# Analog_Front_End.net
KiCad netlist of a schematic drawn in Altium Designer
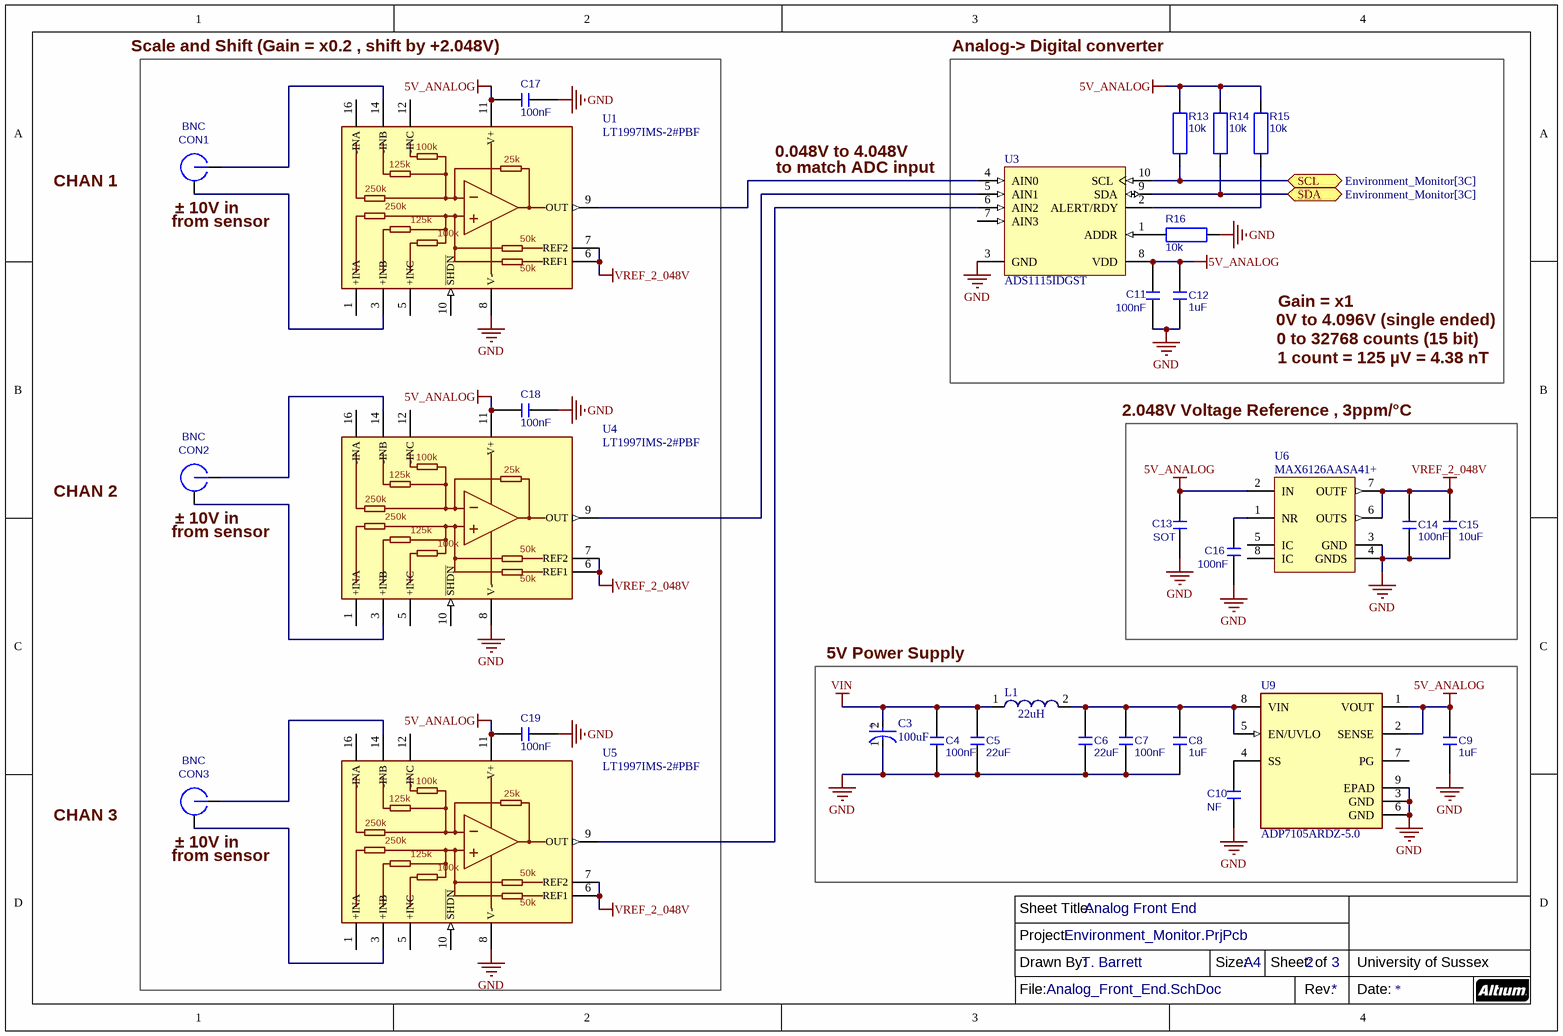
[diagram p0: Analog_Front_End.SchDoc]

(export (version "E")
  (design (tool "Eeschema 10.0.6"))
  (components
    (comp (ref "C3")
      (value "100uF")
      (footprint "FP-865080657017-MFG")
      (description "CAP ALUM 150UF 20% 50V SMD")
      (fields (field (name "TOLERANCE") "20%"))
      (libsource (lib "Altium Content Vault") (part "cf48714ba7e38822c1575c7ec0b6d1f"))
    )
    (comp (ref "C4")
      (value "100nF")
      (footprint "CAPACITOR SMD 1206")
      (description "Ceramic chip capacitor 1206")
      (fields (field (name "Comment") "Capacitor SMD 1206"))
      (libsource (lib "TB_Capacitors") (part "Capacitor SMD 1206"))
    )
    (comp (ref "C5")
      (value "22uF")
      (footprint "CAPACITOR SMD 1206")
      (description "Ceramic chip capacitor 1206")
      (fields (field (name "Comment") "Capacitor SMD 1206"))
      (libsource (lib "TB_Capacitors") (part "Capacitor SMD 1206"))
    )
    (comp (ref "C6")
      (value "22uF")
      (footprint "CAPACITOR SMD 1206")
      (description "Ceramic chip capacitor 1206")
      (fields (field (name "Comment") "Capacitor SMD 1206"))
      (libsource (lib "TB_Capacitors") (part "Capacitor SMD 1206"))
    )
    (comp (ref "C7")
      (value "100nF")
      (footprint "CAPACITOR SMD 1206")
      (description "Ceramic chip capacitor 1206")
      (fields (field (name "Comment") "Capacitor SMD 1206"))
      (libsource (lib "TB_Capacitors") (part "Capacitor SMD 1206"))
    )
    (comp (ref "C8")
      (value "1uF")
      (footprint "CAPACITOR SMD 1206")
      (description "Ceramic chip capacitor 1206")
      (fields (field (name "Comment") "Capacitor SMD 1206"))
      (libsource (lib "TB_Capacitors") (part "Capacitor SMD 1206"))
    )
    (comp (ref "C9")
      (value "1uF")
      (footprint "CAPACITOR SMD 1206")
      (description "Ceramic chip capacitor 1206")
      (fields (field (name "Comment") "Capacitor SMD 1206"))
      (libsource (lib "TB_Capacitors") (part "Capacitor SMD 1206"))
    )
    (comp (ref "C10")
      (value "NF")
      (footprint "CAPACITOR SMD 0805")
      (description "Ceramic chip capacitor 0805")
      (fields (field (name "Comment") "Capacitor SMD 0805"))
      (libsource (lib "TB_Capacitors") (part "Capacitor SMD 0805"))
    )
    (comp (ref "C11")
      (value "100nF")
      (footprint "CAPACITOR SMD 0805")
      (description "Ceramic chip capacitor 0805")
      (fields (field (name "Comment") "Capacitor SMD 0805"))
      (libsource (lib "TB_Capacitors") (part "Capacitor SMD 0805"))
    )
    (comp (ref "C12")
      (value "1uF")
      (footprint "CAPACITOR SMD 1206")
      (description "Ceramic chip capacitor 1206")
      (fields (field (name "Comment") "Capacitor SMD 1206"))
      (libsource (lib "TB_Capacitors") (part "Capacitor SMD 1206"))
    )
    (comp (ref "C13")
      (value "SOT")
      (footprint "CAPACITOR SMD 1206")
      (description "Ceramic chip capacitor 1206")
      (fields (field (name "Comment") "Capacitor SMD 1206"))
      (libsource (lib "TB_Capacitors") (part "Capacitor SMD 1206"))
    )
    (comp (ref "C14")
      (value "100nF")
      (footprint "CAPACITOR SMD 0805")
      (description "Ceramic chip capacitor 0805")
      (fields (field (name "Comment") "Capacitor SMD 0805"))
      (libsource (lib "TB_Capacitors") (part "Capacitor SMD 0805"))
    )
    (comp (ref "C15")
      (value "10uF")
      (footprint "CAPACITOR SMD 1206")
      (description "Ceramic chip capacitor 1206")
      (fields (field (name "Comment") "Capacitor SMD 1206"))
      (libsource (lib "TB_Capacitors") (part "Capacitor SMD 1206"))
    )
    (comp (ref "C16")
      (value "100nF")
      (footprint "CAPACITOR SMD 0805")
      (description "Ceramic chip capacitor 0805")
      (fields (field (name "Comment") "Capacitor SMD 0805"))
      (libsource (lib "TB_Capacitors") (part "Capacitor SMD 0805"))
    )
    (comp (ref "C17")
      (value "100nF")
      (footprint "CAPACITOR SMD 0805")
      (description "Ceramic chip capacitor 0805")
      (fields (field (name "Comment") "Capacitor SMD 0805"))
      (libsource (lib "TB_Capacitors") (part "Capacitor SMD 0805"))
    )
    (comp (ref "C18")
      (value "100nF")
      (footprint "CAPACITOR SMD 0805")
      (description "Ceramic chip capacitor 0805")
      (fields (field (name "Comment") "Capacitor SMD 0805"))
      (libsource (lib "TB_Capacitors") (part "Capacitor SMD 0805"))
    )
    (comp (ref "C19")
      (value "100nF")
      (footprint "CAPACITOR SMD 0805")
      (description "Ceramic chip capacitor 0805")
      (fields (field (name "Comment") "Capacitor SMD 0805"))
      (libsource (lib "TB_Capacitors") (part "Capacitor SMD 0805"))
    )
    (comp (ref "CON1")
      (value "BNC")
      (footprint "BNC B6252H5-NPP3G-50")
      (libsource (lib "TB_Connectors") (part "BNC B6252H5-NPP3G-50"))
    )
    (comp (ref "CON2")
      (value "BNC")
      (footprint "BNC B6252H5-NPP3G-50")
      (libsource (lib "TB_Connectors") (part "BNC B6252H5-NPP3G-50"))
    )
    (comp (ref "CON3")
      (value "BNC")
      (footprint "BNC B6252H5-NPP3G-50")
      (libsource (lib "TB_Connectors") (part "BNC B6252H5-NPP3G-50"))
    )
    (comp (ref "L1")
      (value "22uH")
      (footprint "WE-LQS 4018")
      (description "WE-LQS SMD Power Inductor, L=33 µH")
      (fields (field (name "MANUFACTURER") "Wuerth Elektronik") (field (name "PARTNUMBER") "74404042330"))
      (libsource (lib "Altium Content Vault") (part "WE-IND-INDUCTOR-2"))
    )
    (comp (ref "R13")
      (value "10k")
      (footprint "RESISTOR SMD 0805")
      (description "Resistor, SMD, 0805")
      (fields (field (name "Comment") "Resistor SMD 0805"))
      (libsource (lib "TB_Resistors") (part "Resistor SMD 0805"))
    )
    (comp (ref "R14")
      (value "10k")
      (footprint "RESISTOR SMD 0805")
      (description "Resistor, SMD, 0805")
      (fields (field (name "Comment") "Resistor SMD 0805"))
      (libsource (lib "TB_Resistors") (part "Resistor SMD 0805"))
    )
    (comp (ref "R15")
      (value "10k")
      (footprint "RESISTOR SMD 0805")
      (description "Resistor, SMD, 0805")
      (fields (field (name "Comment") "Resistor SMD 0805"))
      (libsource (lib "TB_Resistors") (part "Resistor SMD 0805"))
    )
    (comp (ref "R16")
      (value "10k")
      (footprint "RESISTOR SMD 0805")
      (description "Resistor, SMD, 0805")
      (fields (field (name "Comment") "Resistor SMD 0805"))
      (libsource (lib "TB_Resistors") (part "Resistor SMD 0805"))
    )
    (comp (ref "U1")
      (value "LT1997IMS-2#PBF")
      (footprint "MSOP-16 (12 pin variation)")
      (description "IC OPAMP GP 1 CIRCUIT 16MSOP")
      (libsource (lib "TB_ICs") (part "LT1997-2"))
    )
    (comp (ref "U3")
      (value "ADS1115IDGST")
      (footprint "VSSOP 10PIN")
      (fields (field (name "MANUFACTURER") "Texas Instruments"))
      (libsource (lib "TB_ICs") (part "ADS1115"))
    )
    (comp (ref "U4")
      (value "LT1997IMS-2#PBF")
      (footprint "MSOP-16 (12 pin variation)")
      (description "IC OPAMP GP 1 CIRCUIT 16MSOP")
      (libsource (lib "TB_ICs") (part "LT1997-2"))
    )
    (comp (ref "U5")
      (value "LT1997IMS-2#PBF")
      (footprint "MSOP-16 (12 pin variation)")
      (description "IC OPAMP GP 1 CIRCUIT 16MSOP")
      (libsource (lib "TB_ICs") (part "LT1997-2"))
    )
    (comp (ref "U6")
      (value "MAX6126AASA41+")
      (footprint "SOIC_N 8-pin")
      (description "Ultra-High-Precision, Ultra-Low-Noise, Series Voltage Reference, 8-Pin SOIC")
      (fields (field (name "MANUFACTURER") "Maxim"))
      (libsource (lib "TB_ICs") (part "MAX6126"))
    )
    (comp (ref "U9")
      (value "ADP7105ARDZ-5.0")
      (footprint "NSOIC-EP-8")
      (description "ANALOG DEVICES 20 V, 500 mA, Low Noise LDO Regulator")
      (libsource (lib "TB_ICs") (part "ADP7105"))
    )
  )
  (nets
    (net (code "1") (name "/SCL") (class "Default")
      (node (ref "R13") (pin "1") (pinfunction "1_1") (pintype "passive"))
      (node (ref "U3") (pin "10") (pinfunction "SCL_10") (pintype "input"))
    )
    (net (code "2") (name "/SDA") (class "Default")
      (node (ref "R14") (pin "1") (pinfunction "1_1") (pintype "passive"))
      (node (ref "U3") (pin "9") (pinfunction "SDA_9") (pintype "bidirectional"))
    )
    (net (code "3") (name "5V_ANALOG") (class "Default")
      (node (ref "C11") (pin "2") (pinfunction "2_2") (pintype "passive"))
      (node (ref "C12") (pin "2") (pinfunction "2_2") (pintype "passive"))
      (node (ref "C13") (pin "2") (pinfunction "2_2") (pintype "passive"))
      (node (ref "C17") (pin "2") (pinfunction "2_2") (pintype "passive"))
      (node (ref "C18") (pin "2") (pinfunction "2_2") (pintype "passive"))
      (node (ref "C19") (pin "2") (pinfunction "2_2") (pintype "passive"))
      (node (ref "C9") (pin "2") (pinfunction "2_2") (pintype "passive"))
      (node (ref "R13") (pin "2") (pinfunction "2_2") (pintype "passive"))
      (node (ref "R14") (pin "2") (pinfunction "2_2") (pintype "passive"))
      (node (ref "R15") (pin "2") (pinfunction "2_2") (pintype "passive"))
      (node (ref "U1") (pin "11") (pinfunction "V+_11") (pintype "power_in"))
      (node (ref "U3") (pin "8") (pinfunction "VDD_8") (pintype "power_in"))
      (node (ref "U4") (pin "11") (pinfunction "V+_11") (pintype "power_in"))
      (node (ref "U5") (pin "11") (pinfunction "V+_11") (pintype "power_in"))
      (node (ref "U6") (pin "2") (pinfunction "IN_2") (pintype "power_in"))
      (node (ref "U9") (pin "1") (pinfunction "VOUT_1") (pintype "passive"))
      (node (ref "U9") (pin "2") (pinfunction "SENSE_2") (pintype "passive"))
    )
    (net (code "4") (name "GND") (class "Default")
      (node (ref "C10") (pin "1") (pinfunction "1_1") (pintype "passive"))
      (node (ref "C11") (pin "1") (pinfunction "1_1") (pintype "passive"))
      (node (ref "C12") (pin "1") (pinfunction "1_1") (pintype "passive"))
      (node (ref "C13") (pin "1") (pinfunction "1_1") (pintype "passive"))
      (node (ref "C14") (pin "1") (pinfunction "1_1") (pintype "passive"))
      (node (ref "C15") (pin "1") (pinfunction "1_1") (pintype "passive"))
      (node (ref "C16") (pin "1") (pinfunction "1_1") (pintype "passive"))
      (node (ref "C17") (pin "1") (pinfunction "1_1") (pintype "passive"))
      (node (ref "C18") (pin "1") (pinfunction "1_1") (pintype "passive"))
      (node (ref "C19") (pin "1") (pinfunction "1_1") (pintype "passive"))
      (node (ref "C3") (pin "1") (pinfunction "C_1") (pintype "passive"))
      (node (ref "C4") (pin "1") (pinfunction "1_1") (pintype "passive"))
      (node (ref "C5") (pin "1") (pinfunction "1_1") (pintype "passive"))
      (node (ref "C6") (pin "1") (pinfunction "1_1") (pintype "passive"))
      (node (ref "C7") (pin "1") (pinfunction "1_1") (pintype "passive"))
      (node (ref "C8") (pin "1") (pinfunction "1_1") (pintype "passive"))
      (node (ref "C9") (pin "1") (pinfunction "1_1") (pintype "passive"))
      (node (ref "R16") (pin "1") (pinfunction "1_1") (pintype "passive"))
      (node (ref "U1") (pin "8") (pinfunction "V-_8") (pintype "power_in"))
      (node (ref "U3") (pin "3") (pinfunction "GND_3") (pintype "power_in"))
      (node (ref "U4") (pin "8") (pinfunction "V-_8") (pintype "power_in"))
      (node (ref "U5") (pin "8") (pinfunction "V-_8") (pintype "power_in"))
      (node (ref "U6") (pin "3") (pinfunction "GND_3") (pintype "power_in"))
      (node (ref "U6") (pin "4") (pinfunction "GNDS_4") (pintype "power_in"))
      (node (ref "U9") (pin "3") (pinfunction "GND_3") (pintype "power_in"))
      (node (ref "U9") (pin "6") (pinfunction "GND_6") (pintype "power_in"))
      (node (ref "U9") (pin "9") (pinfunction "EPAD_9") (pintype "power_in"))
    )
    (net (code "5") (name "Net-(U1-+INB)") (class "Default")
      (node (ref "CON1") (pin "2") (pintype "passive"))
      (node (ref "U1") (pin "3") (pinfunction "+INB_3") (pintype "tri_state"))
    )
    (net (code "6") (name "Net-(U1--INB)") (class "Default")
      (node (ref "CON1") (pin "1") (pintype "passive"))
      (node (ref "U1") (pin "14") (pinfunction "-INB_14") (pintype "tri_state"))
    )
    (net (code "7") (name "Net-(U1-OUT)") (class "Default")
      (node (ref "U1") (pin "9") (pinfunction "OUT_9") (pintype "output"))
      (node (ref "U3") (pin "4") (pinfunction "AIN0_4") (pintype "input"))
    )
    (net (code "8") (name "Net-(U3-ADDR)") (class "Default")
      (node (ref "R16") (pin "2") (pinfunction "2_2") (pintype "passive"))
      (node (ref "U3") (pin "1") (pinfunction "ADDR_1") (pintype "input"))
    )
    (net (code "9") (name "Net-(U3-AIN1)") (class "Default")
      (node (ref "U3") (pin "5") (pinfunction "AIN1_5") (pintype "input"))
      (node (ref "U4") (pin "9") (pinfunction "OUT_9") (pintype "output"))
    )
    (net (code "10") (name "Net-(U3-AIN2)") (class "Default")
      (node (ref "U3") (pin "6") (pinfunction "AIN2_6") (pintype "input"))
      (node (ref "U5") (pin "9") (pinfunction "OUT_9") (pintype "output"))
    )
    (net (code "11") (name "Net-(U3-ALERT{slash}RDY)") (class "Default")
      (node (ref "R15") (pin "1") (pinfunction "1_1") (pintype "passive"))
      (node (ref "U3") (pin "2") (pinfunction "ALERT/RDY_2") (pintype "open_collector"))
    )
    (net (code "12") (name "Net-(U4-+INB)") (class "Default")
      (node (ref "CON2") (pin "2") (pintype "passive"))
      (node (ref "U4") (pin "3") (pinfunction "+INB_3") (pintype "tri_state"))
    )
    (net (code "13") (name "Net-(U4--INB)") (class "Default")
      (node (ref "CON2") (pin "1") (pintype "passive"))
      (node (ref "U4") (pin "14") (pinfunction "-INB_14") (pintype "tri_state"))
    )
    (net (code "14") (name "Net-(U5-+INB)") (class "Default")
      (node (ref "CON3") (pin "2") (pintype "passive"))
      (node (ref "U5") (pin "3") (pinfunction "+INB_3") (pintype "tri_state"))
    )
    (net (code "15") (name "Net-(U5--INB)") (class "Default")
      (node (ref "CON3") (pin "1") (pintype "passive"))
      (node (ref "U5") (pin "14") (pinfunction "-INB_14") (pintype "tri_state"))
    )
    (net (code "16") (name "Net-(U6-NR)") (class "Default")
      (node (ref "C16") (pin "2") (pinfunction "2_2") (pintype "passive"))
      (node (ref "U6") (pin "1") (pinfunction "NR_1") (pintype "passive"))
    )
    (net (code "17") (name "Net-(U9-EN{slash}UVLO)") (class "Default")
      (node (ref "C6") (pin "2") (pinfunction "2_2") (pintype "passive"))
      (node (ref "C7") (pin "2") (pinfunction "2_2") (pintype "passive"))
      (node (ref "C8") (pin "2") (pinfunction "2_2") (pintype "passive"))
      (node (ref "L1") (pin "2") (pinfunction "2_2") (pintype "passive"))
      (node (ref "U9") (pin "5") (pinfunction "EN/UVLO_5") (pintype "input"))
      (node (ref "U9") (pin "8") (pinfunction "VIN_8") (pintype "passive"))
    )
    (net (code "18") (name "Net-(U9-SS)") (class "Default")
      (node (ref "C10") (pin "2") (pinfunction "2_2") (pintype "passive"))
      (node (ref "U9") (pin "4") (pinfunction "SS_4") (pintype "passive"))
    )
    (net (code "19") (name "VIN") (class "Default")
      (node (ref "C3") (pin "2") (pinfunction "A_2") (pintype "passive"))
      (node (ref "C4") (pin "2") (pinfunction "2_2") (pintype "passive"))
      (node (ref "C5") (pin "2") (pinfunction "2_2") (pintype "passive"))
      (node (ref "L1") (pin "1") (pinfunction "1_1") (pintype "passive"))
    )
    (net (code "20") (name "VREF_2_048V") (class "Default")
      (node (ref "C14") (pin "2") (pinfunction "2_2") (pintype "passive"))
      (node (ref "C15") (pin "2") (pinfunction "2_2") (pintype "passive"))
      (node (ref "U1") (pin "6") (pinfunction "REF1_6") (pintype "passive"))
      (node (ref "U1") (pin "7") (pinfunction "REF2_7") (pintype "passive"))
      (node (ref "U4") (pin "6") (pinfunction "REF1_6") (pintype "passive"))
      (node (ref "U4") (pin "7") (pinfunction "REF2_7") (pintype "passive"))
      (node (ref "U5") (pin "6") (pinfunction "REF1_6") (pintype "passive"))
      (node (ref "U5") (pin "7") (pinfunction "REF2_7") (pintype "passive"))
      (node (ref "U6") (pin "6") (pinfunction "OUTS_6") (pintype "output"))
      (node (ref "U6") (pin "7") (pinfunction "OUTF_7") (pintype "output"))
    )
    (net (code "21") (name "unconnected-(CON1-Pad3)") (class "Default")
      (node (ref "CON1") (pin "3") (pintype "passive"))
    )
    (net (code "22") (name "unconnected-(CON1-Pad4)") (class "Default")
      (node (ref "CON1") (pin "4") (pintype "passive"))
    )
    (net (code "23") (name "unconnected-(CON2-Pad3)") (class "Default")
      (node (ref "CON2") (pin "3") (pintype "passive"))
    )
    (net (code "24") (name "unconnected-(CON2-Pad4)") (class "Default")
      (node (ref "CON2") (pin "4") (pintype "passive"))
    )
    (net (code "25") (name "unconnected-(CON3-Pad3)") (class "Default")
      (node (ref "CON3") (pin "3") (pintype "passive"))
    )
    (net (code "26") (name "unconnected-(CON3-Pad4)") (class "Default")
      (node (ref "CON3") (pin "4") (pintype "passive"))
    )
    (net (code "27") (name "unconnected-(U1-+INA-Pad1)") (class "Default")
      (node (ref "U1") (pin "1") (pinfunction "+INA_1") (pintype "tri_state"))
    )
    (net (code "28") (name "unconnected-(U1-+INC-Pad5)") (class "Default")
      (node (ref "U1") (pin "5") (pinfunction "+INC_5") (pintype "tri_state"))
    )
    (net (code "29") (name "unconnected-(U1--INA-Pad16)") (class "Default")
      (node (ref "U1") (pin "16") (pinfunction "-INA_16") (pintype "tri_state"))
    )
    (net (code "30") (name "unconnected-(U1--INC-Pad12)") (class "Default")
      (node (ref "U1") (pin "12") (pinfunction "-INC_12") (pintype "tri_state"))
    )
    (net (code "31") (name "unconnected-(U1-~{SHDN}-Pad10)") (class "Default")
      (node (ref "U1") (pin "10") (pinfunction "~{SHDN}_10") (pintype "input"))
    )
    (net (code "32") (name "unconnected-(U3-AIN3-Pad7)") (class "Default")
      (node (ref "U3") (pin "7") (pinfunction "AIN3_7") (pintype "input"))
    )
    (net (code "33") (name "unconnected-(U4-+INA-Pad1)") (class "Default")
      (node (ref "U4") (pin "1") (pinfunction "+INA_1") (pintype "tri_state"))
    )
    (net (code "34") (name "unconnected-(U4-+INC-Pad5)") (class "Default")
      (node (ref "U4") (pin "5") (pinfunction "+INC_5") (pintype "tri_state"))
    )
    (net (code "35") (name "unconnected-(U4--INA-Pad16)") (class "Default")
      (node (ref "U4") (pin "16") (pinfunction "-INA_16") (pintype "tri_state"))
    )
    (net (code "36") (name "unconnected-(U4--INC-Pad12)") (class "Default")
      (node (ref "U4") (pin "12") (pinfunction "-INC_12") (pintype "tri_state"))
    )
    (net (code "37") (name "unconnected-(U4-~{SHDN}-Pad10)") (class "Default")
      (node (ref "U4") (pin "10") (pinfunction "~{SHDN}_10") (pintype "input"))
    )
    (net (code "38") (name "unconnected-(U5-+INA-Pad1)") (class "Default")
      (node (ref "U5") (pin "1") (pinfunction "+INA_1") (pintype "tri_state"))
    )
    (net (code "39") (name "unconnected-(U5-+INC-Pad5)") (class "Default")
      (node (ref "U5") (pin "5") (pinfunction "+INC_5") (pintype "tri_state"))
    )
    (net (code "40") (name "unconnected-(U5--INA-Pad16)") (class "Default")
      (node (ref "U5") (pin "16") (pinfunction "-INA_16") (pintype "tri_state"))
    )
    (net (code "41") (name "unconnected-(U5--INC-Pad12)") (class "Default")
      (node (ref "U5") (pin "12") (pinfunction "-INC_12") (pintype "tri_state"))
    )
    (net (code "42") (name "unconnected-(U5-~{SHDN}-Pad10)") (class "Default")
      (node (ref "U5") (pin "10") (pinfunction "~{SHDN}_10") (pintype "input"))
    )
    (net (code "43") (name "unconnected-(U6-IC-Pad5)") (class "Default")
      (node (ref "U6") (pin "5") (pinfunction "IC_5") (pintype "passive"))
    )
    (net (code "44") (name "unconnected-(U6-IC-Pad8)") (class "Default")
      (node (ref "U6") (pin "8") (pinfunction "IC_8") (pintype "passive"))
    )
    (net (code "45") (name "unconnected-(U9-PG-Pad7)") (class "Default")
      (node (ref "U9") (pin "7") (pinfunction "PG_7") (pintype "passive"))
    )
  )
)
